# Desklamp_H201005_V1.net
KiCad netlist of a schematic drawn in EAGLE
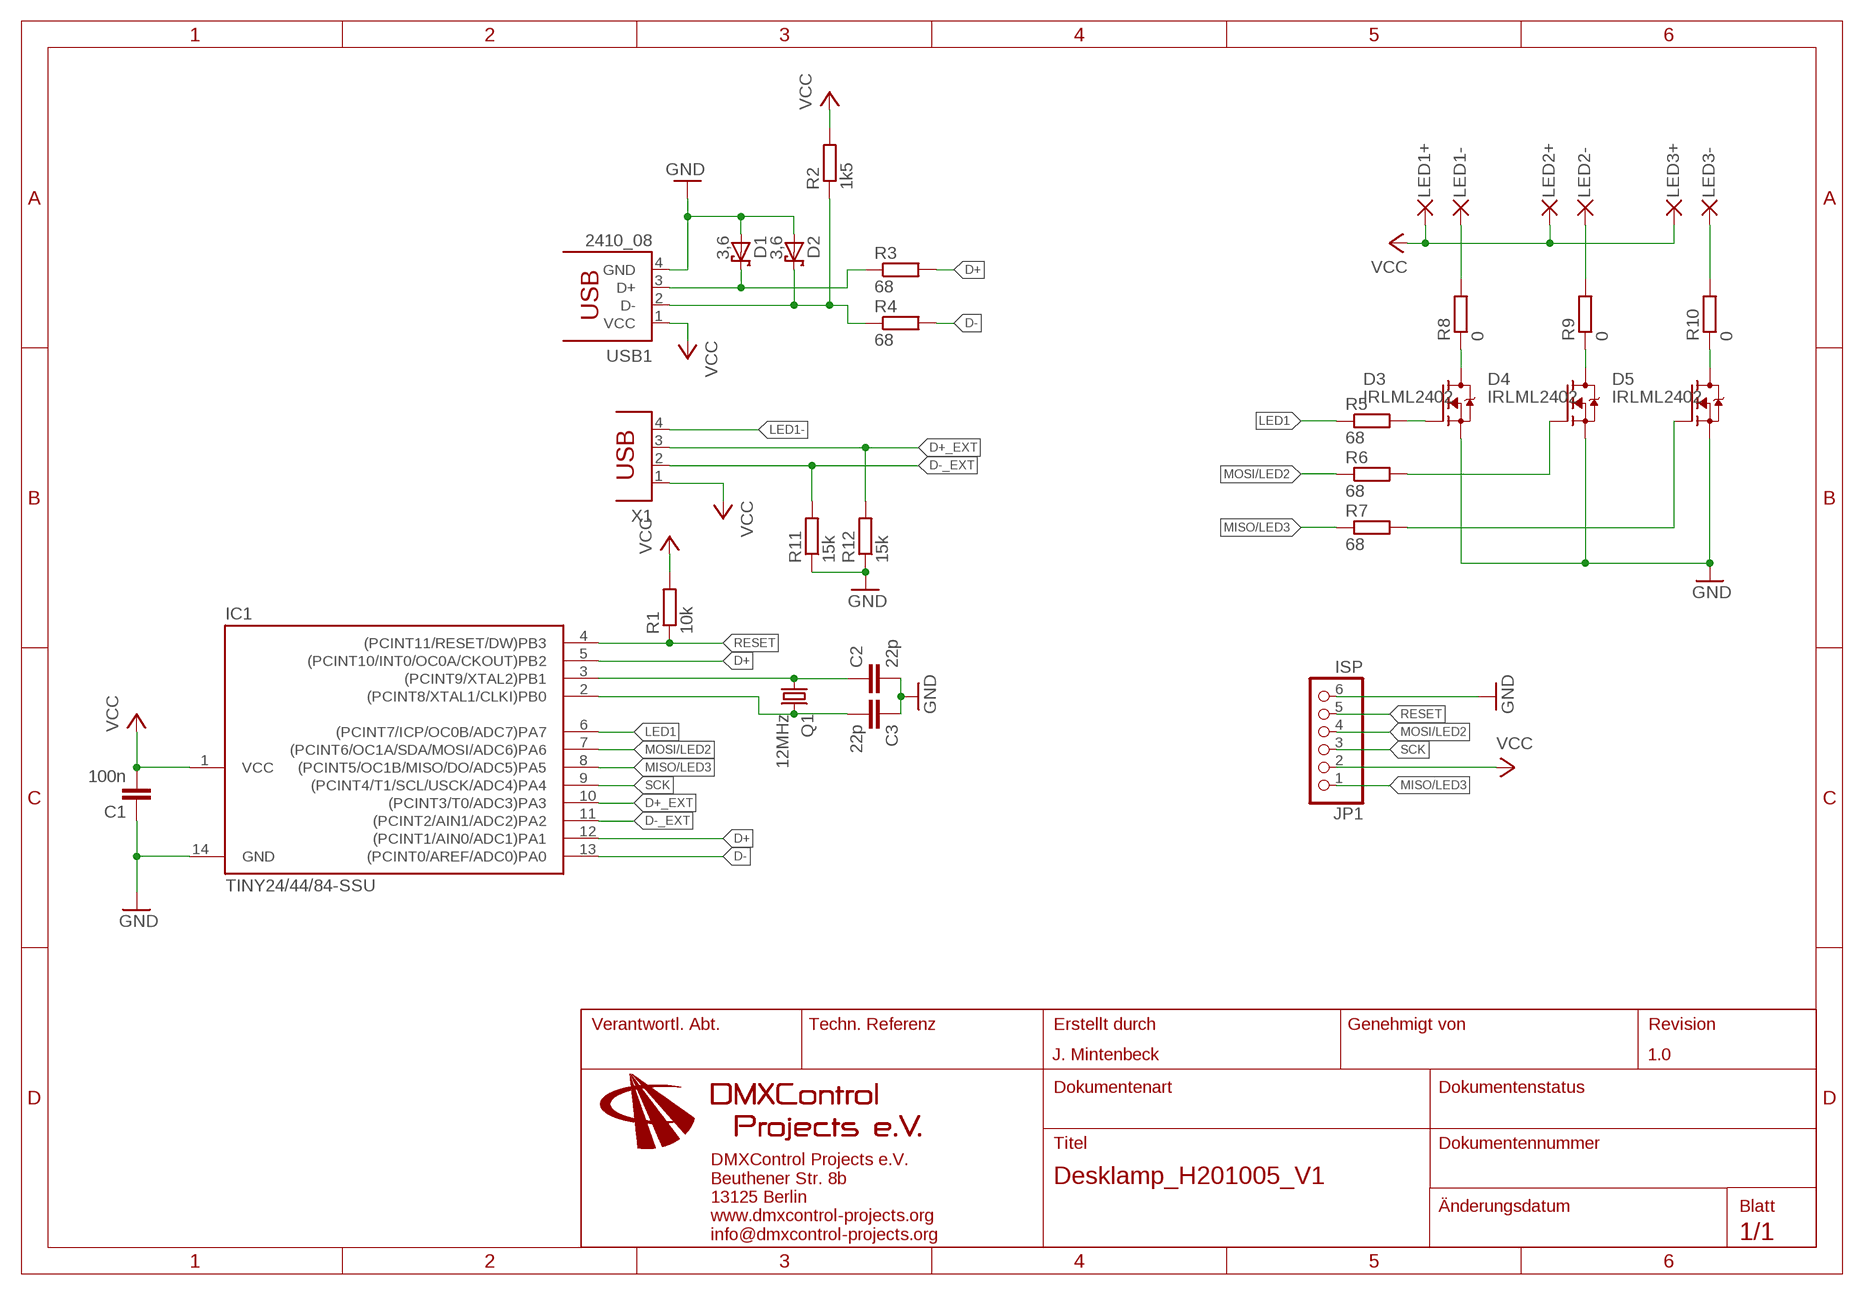
[diagram p0: schematic, sheet 1]

(export (version "E")
  (design (tool "Eeschema 10.0.6"))
  (components
    (comp (ref "C1")
      (value "100n")
      (footprint "eagle-import:C0805")
      (fields (field (name "PARTNO") "CC0805KRX7R9BB104"))
      (libsource (lib "eagle-import") (part "C-EUC0805"))
    )
    (comp (ref "C2")
      (value "22p")
      (footprint "eagle-import:C0805")
      (fields (field (name "PARTNO") "VVS-SMD COG 50 V 22 PF G0805"))
      (libsource (lib "eagle-import") (part "C-EUC0805"))
    )
    (comp (ref "C3")
      (value "22p")
      (footprint "eagle-import:C0805")
      (fields (field (name "PARTNO") "VVS-SMD COG 50 V 22 PF G0805"))
      (libsource (lib "eagle-import") (part "C-EUC0805"))
    )
    (comp (ref "D1")
      (value "3,6")
      (footprint "eagle-import:SOT23")
      (fields (field (name "PARTNO") "BZX84C3V6"))
      (libsource (lib "eagle-import") (part "BAS40"))
    )
    (comp (ref "D2")
      (value "3,6")
      (footprint "eagle-import:SOT23")
      (fields (field (name "PARTNO") "BZX84C3V6"))
      (libsource (lib "eagle-import") (part "BAS40"))
    )
    (comp (ref "D3")
      (value "IRLML2402")
      (footprint "eagle-import:SOT23")
      (fields (field (name "PARTNO") "IRLML2402PBF"))
      (libsource (lib "eagle-import") (part "IRLML2402"))
    )
    (comp (ref "D4")
      (value "IRLML2402")
      (footprint "eagle-import:SOT23")
      (fields (field (name "PARTNO") "IRLML2402PBF"))
      (libsource (lib "eagle-import") (part "IRLML2402"))
    )
    (comp (ref "D5")
      (value "IRLML2402")
      (footprint "eagle-import:SOT23")
      (fields (field (name "PARTNO") "IRLML2402PBF"))
      (libsource (lib "eagle-import") (part "IRLML2402"))
    )
    (comp (ref "IC1")
      (value "TINY24/44/84-SSU")
      (footprint "eagle-import:SOIC14")
      (fields (field (name "PARTNO") "ATTINY44ASSU"))
      (libsource (lib "eagle-import") (part "TINY24/44/84-SSU"))
    )
    (comp (ref "JP1")
      (value "ISP")
      (footprint "eagle-import:1X06M")
      (libsource (lib "eagle-import") (part "PINHD-1X06_2.00"))
    )
    (comp (ref "PAD1")
      (value "LED1+")
      (footprint "eagle-import:SMD1,27-2,54")
      (libsource (lib "eagle-import") (part "SMD2"))
    )
    (comp (ref "PAD2")
      (value "LED1-")
      (footprint "eagle-import:SMD1,27-2,54")
      (libsource (lib "eagle-import") (part "SMD2"))
    )
    (comp (ref "PAD3")
      (value "LED2+")
      (footprint "eagle-import:SMD1,27-2,54")
      (libsource (lib "eagle-import") (part "SMD2"))
    )
    (comp (ref "PAD4")
      (value "LED2-")
      (footprint "eagle-import:SMD1,27-2,54")
      (libsource (lib "eagle-import") (part "SMD2"))
    )
    (comp (ref "PAD5")
      (value "LED3+")
      (footprint "eagle-import:SMD1,27-2,54")
      (libsource (lib "eagle-import") (part "SMD2"))
    )
    (comp (ref "PAD6")
      (value "LED3-")
      (footprint "eagle-import:SMD1,27-2,54")
      (libsource (lib "eagle-import") (part "SMD2"))
    )
    (comp (ref "Q1")
      (value "12MHz")
      (footprint "eagle-import:HC49UP")
      (fields (field (name "PARTNO") "12.000MHZ 49USMX/30/50/40/18PF/ATF"))
      (libsource (lib "eagle-import") (part "CRYSTALHC49UP"))
    )
    (comp (ref "R1")
      (value "10k")
      (footprint "eagle-import:R0805")
      (fields (field (name "PARTNO") "RC0805 FR-07 10 K"))
      (libsource (lib "eagle-import") (part "R-EU_R0805"))
    )
    (comp (ref "R2")
      (value "1k5")
      (footprint "eagle-import:R0805")
      (fields (field (name "PARTNO") "RC0805 FR-07 1,5 K"))
      (libsource (lib "eagle-import") (part "R-EU_R0805"))
    )
    (comp (ref "R3")
      (value "68")
      (footprint "eagle-import:R0805")
      (fields (field (name "PARTNO") "RC0805 FR-07 68 R"))
      (libsource (lib "eagle-import") (part "R-EU_R0805"))
    )
    (comp (ref "R4")
      (value "68")
      (footprint "eagle-import:R0805")
      (fields (field (name "PARTNO") "RC0805 FR-07 68 R"))
      (libsource (lib "eagle-import") (part "R-EU_R0805"))
    )
    (comp (ref "R5")
      (value "68")
      (footprint "eagle-import:R0805")
      (fields (field (name "PARTNO") "RC0805 FR-07 68 R"))
      (libsource (lib "eagle-import") (part "R-EU_R0805"))
    )
    (comp (ref "R6")
      (value "68")
      (footprint "eagle-import:R0805")
      (fields (field (name "PARTNO") "RC0805 FR-07 68 R"))
      (libsource (lib "eagle-import") (part "R-EU_R0805"))
    )
    (comp (ref "R7")
      (value "68")
      (footprint "eagle-import:R0805")
      (fields (field (name "PARTNO") "RC0805 FR-07 68 R"))
      (libsource (lib "eagle-import") (part "R-EU_R0805"))
    )
    (comp (ref "R8")
      (value "0")
      (footprint "eagle-import:R0805")
      (fields (field (name "PARTNO") "RC0805 FR-07 0 R"))
      (libsource (lib "eagle-import") (part "R-EU_R0805"))
    )
    (comp (ref "R9")
      (value "0")
      (footprint "eagle-import:R0805")
      (fields (field (name "PARTNO") "RC0805 FR-07 0 R"))
      (libsource (lib "eagle-import") (part "R-EU_R0805"))
    )
    (comp (ref "R10")
      (value "0")
      (footprint "eagle-import:R0805")
      (fields (field (name "PARTNO") "RC0805 FR-07 0 R"))
      (libsource (lib "eagle-import") (part "R-EU_R0805"))
    )
    (comp (ref "R11")
      (value "15k")
      (footprint "eagle-import:R0805")
      (fields (field (name "PARTNO") "RC0805 FR-07 15 K"))
      (libsource (lib "eagle-import") (part "R-EU_R0805"))
    )
    (comp (ref "R12")
      (value "15k")
      (footprint "eagle-import:R0805")
      (fields (field (name "PARTNO") "RC0805 FR-07 15 K"))
      (libsource (lib "eagle-import") (part "R-EU_R0805"))
    )
    (comp (ref "USB1")
      (value "2410_08")
      (footprint "eagle-import:2410_08")
      (fields (field (name "PARTNO") "2410 08"))
      (libsource (lib "eagle-import") (part "2410_08"))
    )
    (comp (ref "X1")
      (value "PN87520")
      (footprint "eagle-import:PN87520")
      (libsource (lib "eagle-import") (part "PN87520"))
    )
  )
  (nets
    (net (code "1") (name "D+") (class "Default")
      (node (ref "IC1") (pin "12") (pinfunction "(PCINT1/AIN0/ADC1)PA1_12") (pintype "bidirectional"))
      (node (ref "IC1") (pin "5") (pinfunction "(PCINT10/INT0/OC0A/CKOUT)PB2_5") (pintype "bidirectional"))
      (node (ref "R3") (pin "2") (pinfunction "2_2") (pintype "passive"))
    )
    (net (code "2") (name "D+_EXT") (class "Default")
      (node (ref "IC1") (pin "10") (pinfunction "(PCINT3/T0/ADC3)PA3_10") (pintype "bidirectional"))
      (node (ref "R12") (pin "2") (pinfunction "2_2") (pintype "passive"))
      (node (ref "X1") (pin "3") (pinfunction "3_3") (pintype "passive"))
    )
    (net (code "3") (name "D-") (class "Default")
      (node (ref "IC1") (pin "13") (pinfunction "(PCINT0/AREF/ADC0)PA0_13") (pintype "bidirectional"))
      (node (ref "R4") (pin "2") (pinfunction "2_2") (pintype "passive"))
    )
    (net (code "4") (name "D-_EXT") (class "Default")
      (node (ref "IC1") (pin "11") (pinfunction "(PCINT2/AIN1/ADC2)PA2_11") (pintype "bidirectional"))
      (node (ref "R11") (pin "2") (pinfunction "2_2") (pintype "passive"))
      (node (ref "X1") (pin "2") (pinfunction "2_2") (pintype "passive"))
    )
    (net (code "5") (name "GND") (class "Default")
      (node (ref "C1") (pin "1") (pinfunction "1_1") (pintype "passive"))
      (node (ref "C2") (pin "2") (pinfunction "2_2") (pintype "passive"))
      (node (ref "C3") (pin "1") (pinfunction "1_1") (pintype "passive"))
      (node (ref "D1") (pin "1") (pinfunction "A_1") (pintype "passive"))
      (node (ref "D2") (pin "1") (pinfunction "A_1") (pintype "passive"))
      (node (ref "D3") (pin "2") (pinfunction "S_2") (pintype "passive"))
      (node (ref "D4") (pin "2") (pinfunction "S_2") (pintype "passive"))
      (node (ref "D5") (pin "2") (pinfunction "S_2") (pintype "passive"))
      (node (ref "IC1") (pin "14") (pinfunction "GND_14") (pintype "power_in"))
      (node (ref "JP1") (pin "6") (pinfunction "6_6") (pintype "passive"))
      (node (ref "R11") (pin "1") (pinfunction "1_1") (pintype "passive"))
      (node (ref "R12") (pin "1") (pinfunction "1_1") (pintype "passive"))
      (node (ref "USB1") (pin "4") (pinfunction "GND_4") (pintype "passive"))
    )
    (net (code "6") (name "LED1") (class "Default")
      (node (ref "IC1") (pin "6") (pinfunction "(PCINT7/ICP/OC0B/ADC7)PA7_6") (pintype "bidirectional"))
      (node (ref "R5") (pin "1") (pinfunction "1_1") (pintype "passive"))
    )
    (net (code "7") (name "LED1-") (class "Default")
      (node (ref "PAD2") (pin "1") (pinfunction "P_1") (pintype "passive"))
      (node (ref "R8") (pin "2") (pinfunction "2_2") (pintype "passive"))
      (node (ref "X1") (pin "4") (pinfunction "4_4") (pintype "passive"))
    )
    (net (code "8") (name "MISO{slash}LED3") (class "Default")
      (node (ref "IC1") (pin "8") (pinfunction "(PCINT5/OC1B/MISO/DO/ADC5)PA5_8") (pintype "bidirectional"))
      (node (ref "JP1") (pin "1") (pinfunction "1_1") (pintype "passive"))
      (node (ref "R7") (pin "1") (pinfunction "1_1") (pintype "passive"))
    )
    (net (code "9") (name "MOSI{slash}LED2") (class "Default")
      (node (ref "IC1") (pin "7") (pinfunction "(PCINT6/OC1A/SDA/MOSI/ADC6)PA6_7") (pintype "bidirectional"))
      (node (ref "JP1") (pin "4") (pinfunction "4_4") (pintype "passive"))
      (node (ref "R6") (pin "1") (pinfunction "1_1") (pintype "passive"))
    )
    (net (code "10") (name "Net-(D1-C)") (class "Default")
      (node (ref "D1") (pin "3") (pinfunction "C_3") (pintype "passive"))
      (node (ref "R3") (pin "1") (pinfunction "1_1") (pintype "passive"))
      (node (ref "USB1") (pin "3") (pinfunction "D+_3") (pintype "passive"))
    )
    (net (code "11") (name "Net-(D2-C)") (class "Default")
      (node (ref "D2") (pin "3") (pinfunction "C_3") (pintype "passive"))
      (node (ref "R2") (pin "1") (pinfunction "1_1") (pintype "passive"))
      (node (ref "R4") (pin "1") (pinfunction "1_1") (pintype "passive"))
      (node (ref "USB1") (pin "2") (pinfunction "D-_2") (pintype "passive"))
    )
    (net (code "12") (name "Net-(D3-D)") (class "Default")
      (node (ref "D3") (pin "3") (pinfunction "D_3") (pintype "passive"))
      (node (ref "R8") (pin "1") (pinfunction "1_1") (pintype "passive"))
    )
    (net (code "13") (name "Net-(D3-G)") (class "Default")
      (node (ref "D3") (pin "1") (pinfunction "G_1") (pintype "passive"))
      (node (ref "R5") (pin "2") (pinfunction "2_2") (pintype "passive"))
    )
    (net (code "14") (name "Net-(D4-D)") (class "Default")
      (node (ref "D4") (pin "3") (pinfunction "D_3") (pintype "passive"))
      (node (ref "R9") (pin "1") (pinfunction "1_1") (pintype "passive"))
    )
    (net (code "15") (name "Net-(D4-G)") (class "Default")
      (node (ref "D4") (pin "1") (pinfunction "G_1") (pintype "passive"))
      (node (ref "R6") (pin "2") (pinfunction "2_2") (pintype "passive"))
    )
    (net (code "16") (name "Net-(D5-D)") (class "Default")
      (node (ref "D5") (pin "3") (pinfunction "D_3") (pintype "passive"))
      (node (ref "R10") (pin "1") (pinfunction "1_1") (pintype "passive"))
    )
    (net (code "17") (name "Net-(D5-G)") (class "Default")
      (node (ref "D5") (pin "1") (pinfunction "G_1") (pintype "passive"))
      (node (ref "R7") (pin "2") (pinfunction "2_2") (pintype "passive"))
    )
    (net (code "18") (name "Net-(IC1-(PCINT8{slash}XTAL1{slash}CLKI)PB0)") (class "Default")
      (node (ref "C3") (pin "2") (pinfunction "2_2") (pintype "passive"))
      (node (ref "IC1") (pin "2") (pinfunction "(PCINT8/XTAL1/CLKI)PB0_2") (pintype "bidirectional"))
      (node (ref "Q1") (pin "2") (pinfunction "2_2") (pintype "passive"))
    )
    (net (code "19") (name "Net-(IC1-(PCINT9{slash}XTAL2)PB1)") (class "Default")
      (node (ref "C2") (pin "1") (pinfunction "1_1") (pintype "passive"))
      (node (ref "IC1") (pin "3") (pinfunction "(PCINT9/XTAL2)PB1_3") (pintype "bidirectional"))
      (node (ref "Q1") (pin "1") (pinfunction "1_1") (pintype "passive"))
    )
    (net (code "20") (name "Net-(PAD4-P)") (class "Default")
      (node (ref "PAD4") (pin "1") (pinfunction "P_1") (pintype "passive"))
      (node (ref "R9") (pin "2") (pinfunction "2_2") (pintype "passive"))
    )
    (net (code "21") (name "Net-(PAD6-P)") (class "Default")
      (node (ref "PAD6") (pin "1") (pinfunction "P_1") (pintype "passive"))
      (node (ref "R10") (pin "2") (pinfunction "2_2") (pintype "passive"))
    )
    (net (code "22") (name "RESET") (class "Default")
      (node (ref "IC1") (pin "4") (pinfunction "(PCINT11/RESET/DW)PB3_4") (pintype "bidirectional"))
      (node (ref "JP1") (pin "5") (pinfunction "5_5") (pintype "passive"))
      (node (ref "R1") (pin "1") (pinfunction "1_1") (pintype "passive"))
    )
    (net (code "23") (name "SCK") (class "Default")
      (node (ref "IC1") (pin "9") (pinfunction "(PCINT4/T1/SCL/USCK/ADC4)PA4_9") (pintype "bidirectional"))
      (node (ref "JP1") (pin "3") (pinfunction "3_3") (pintype "passive"))
    )
    (net (code "24") (name "VCC") (class "Default")
      (node (ref "C1") (pin "2") (pinfunction "2_2") (pintype "passive"))
      (node (ref "IC1") (pin "1") (pinfunction "VCC_1") (pintype "power_in"))
      (node (ref "JP1") (pin "2") (pinfunction "2_2") (pintype "passive"))
      (node (ref "PAD1") (pin "1") (pinfunction "P_1") (pintype "passive"))
      (node (ref "PAD3") (pin "1") (pinfunction "P_1") (pintype "passive"))
      (node (ref "PAD5") (pin "1") (pinfunction "P_1") (pintype "passive"))
      (node (ref "R1") (pin "2") (pinfunction "2_2") (pintype "passive"))
      (node (ref "R2") (pin "2") (pinfunction "2_2") (pintype "passive"))
      (node (ref "USB1") (pin "1") (pinfunction "VCC_1") (pintype "passive"))
      (node (ref "X1") (pin "1") (pinfunction "1_1") (pintype "passive"))
    )
  )
)
